# PiHAT_v0_2.net
KiCad netlist of a schematic drawn in EAGLE
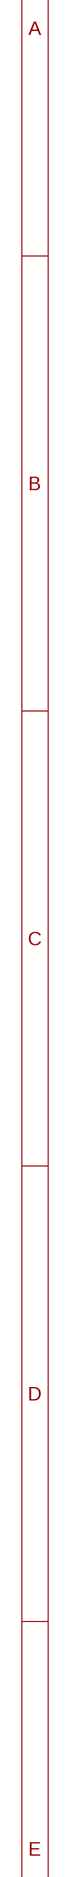
[diagram p0: schematic, sheet 1, part 1 of 2]
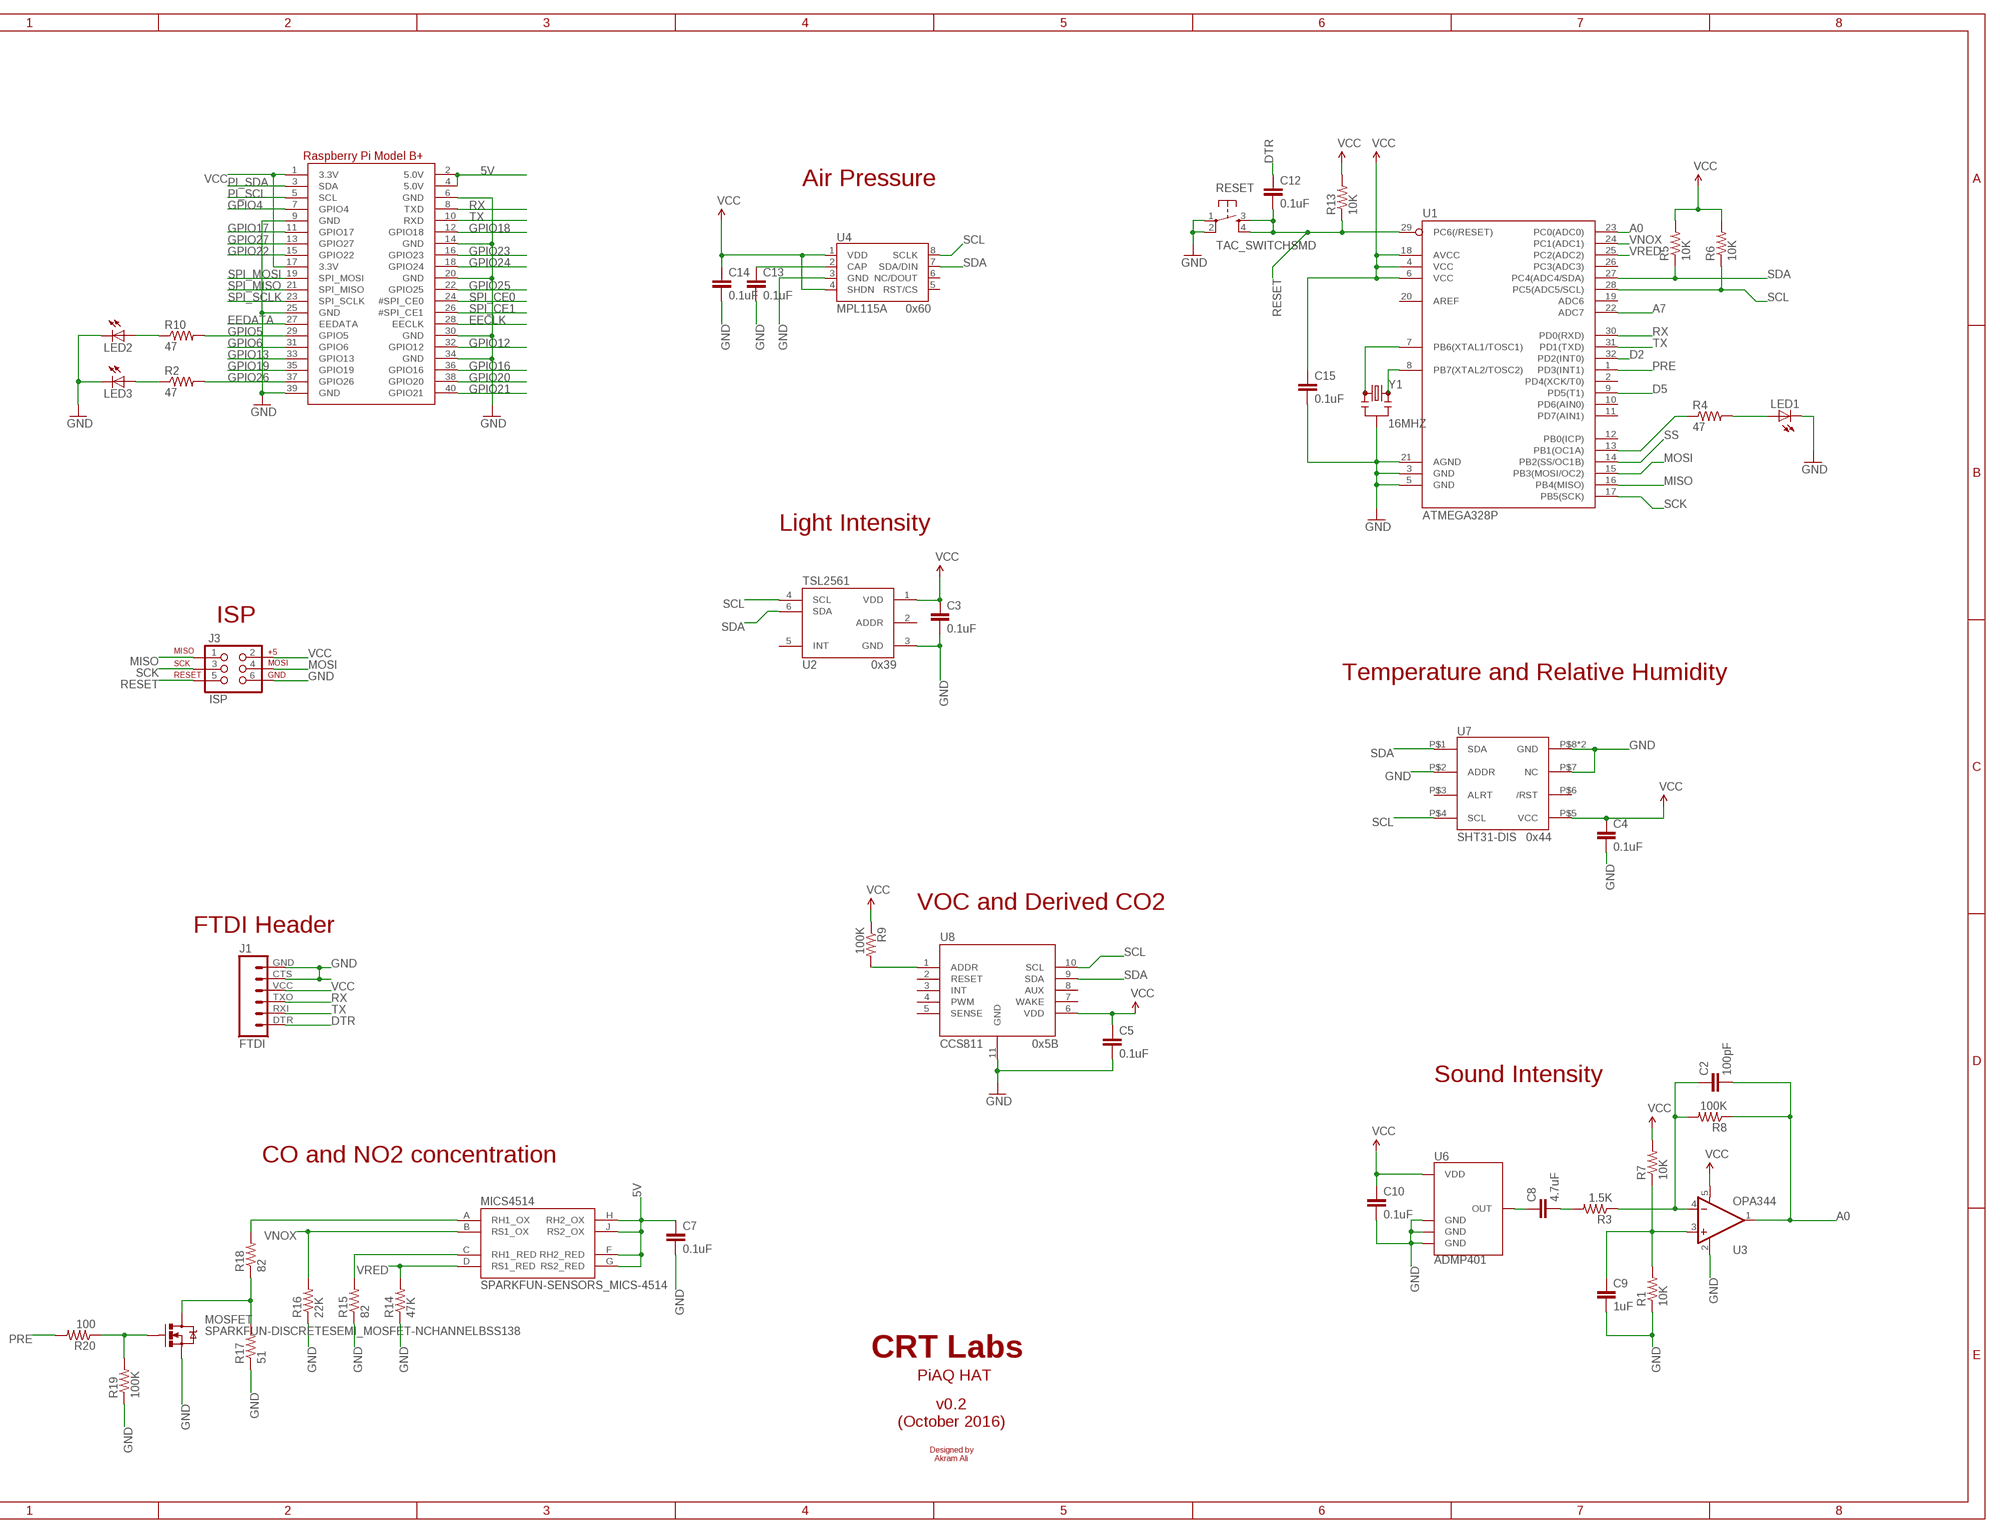
[diagram p1: schematic, sheet 1, part 2 of 2]

(export (version "E")
  (design (tool "Eeschema 10.0.6"))
  (components
    (comp (ref "C2")
      (value "100pF")
      (footprint "eagle-import:0805")
      (fields (field (name "MPN") "CC0805JRNPO9BN101"))
      (libsource (lib "eagle-import") (part "CAP0805"))
    )
    (comp (ref "C3")
      (value "0.1uF")
      (footprint "eagle-import:0805")
      (fields (field (name "MPN") "CC0603KRX7R7BB104"))
      (libsource (lib "eagle-import") (part "SparkFun-Passives_CAP0805"))
    )
    (comp (ref "C4")
      (value "0.1uF")
      (footprint "eagle-import:0805")
      (fields (field (name "MPN") "CC0603KRX7R7BB104"))
      (libsource (lib "eagle-import") (part "SparkFun-Passives_CAP0805"))
    )
    (comp (ref "C5")
      (value "0.1uF")
      (footprint "eagle-import:0805")
      (fields (field (name "MPN") "CC0603KRX7R7BB104"))
      (libsource (lib "eagle-import") (part "SparkFun-Passives_CAP0805"))
    )
    (comp (ref "C7")
      (value "0.1uF")
      (footprint "eagle-import:0805")
      (fields (field (name "MPN") "CC0603KRX7R7BB104"))
      (libsource (lib "eagle-import") (part "SparkFun-Passives_CAP0805"))
    )
    (comp (ref "C8")
      (value "4.7uF")
      (footprint "eagle-import:0805")
      (fields (field (name "MPN") "CC0805KKX5R8BB475"))
      (libsource (lib "eagle-import") (part "CAP0805"))
    )
    (comp (ref "C9")
      (value "1uF")
      (footprint "eagle-import:0805")
      (fields (field (name "MPN") "CC0805KKX7R7BB105"))
      (libsource (lib "eagle-import") (part "CAP0805"))
    )
    (comp (ref "C10")
      (value "0.1uF")
      (footprint "eagle-import:0805")
      (fields (field (name "MPN") "CC0603KRX7R7BB104"))
      (libsource (lib "eagle-import") (part "CAP0805"))
    )
    (comp (ref "C12")
      (value "0.1uF")
      (footprint "eagle-import:0805")
      (fields (field (name "MPN") "CC0603KRX7R7BB104"))
      (libsource (lib "eagle-import") (part "SparkFun-Passives_CAP0805"))
    )
    (comp (ref "C13")
      (value "0.1uF")
      (footprint "eagle-import:0805")
      (fields (field (name "MPN") "CC0603KRX7R7BB104"))
      (libsource (lib "eagle-import") (part "SparkFun-Passives_CAP0805"))
    )
    (comp (ref "C14")
      (value "0.1uF")
      (footprint "eagle-import:0805")
      (fields (field (name "MPN") "CC0603KRX7R7BB104"))
      (libsource (lib "eagle-import") (part "SparkFun-Passives_CAP0805"))
    )
    (comp (ref "C15")
      (value "0.1uF")
      (footprint "eagle-import:0805")
      (fields (field (name "MPN") "CC0603KRX7R7BB104"))
      (libsource (lib "eagle-import") (part "SparkFun-Passives_CAP0805"))
    )
    (comp (ref "J1")
      (value "FTDI")
      (footprint "eagle-import:FTDI_BASIC")
      (fields (field (name "MPN") "FT231XS-R"))
      (libsource (lib "eagle-import") (part "FTDI_BASICPTH"))
    )
    (comp (ref "J3")
      (value "ISP")
      (footprint "eagle-import:2X3")
      (libsource (lib "eagle-import") (part "AVR_SPI_PRG_6PTH"))
    )
    (comp (ref "LED1")
      (value "LEDCHIPLED_0805")
      (footprint "eagle-import:CHIPLED_0805")
      (fields (field (name "MPN") "LY L29K-H1K2-26-Z"))
      (libsource (lib "eagle-import") (part "LEDCHIPLED_0805"))
    )
    (comp (ref "LED2")
      (value "LEDCHIPLED_0805")
      (footprint "eagle-import:CHIPLED_0805")
      (description "LED")
      (fields (field (name "MPN") "LY L29K-H1K2-26-Z"))
      (libsource (lib "eagle-import") (part "LEDCHIPLED_0805"))
    )
    (comp (ref "LED3")
      (value "LEDCHIPLED_0805")
      (footprint "eagle-import:CHIPLED_0805")
      (description "LED")
      (fields (field (name "MPN") "LY L29K-H1K2-26-Z"))
      (libsource (lib "eagle-import") (part "LEDCHIPLED_0805"))
    )
    (comp (ref "MICS4514")
      (value "SPARKFUN-SENSORS_MICS-4514")
      (footprint "eagle-import:SPARKFUN-SENSORS_MICS_10-SMD")
      (fields (field (name "MANF") "SensorTech") (field (name "MPN") "MiCS-4514"))
      (libsource (lib "eagle-import") (part "SPARKFUN-SENSORS_MICS-4514"))
    )
    (comp (ref "MOSFET")
      (value "SPARKFUN-DISCRETESEMI_MOSFET-NCHANNELBSS138")
      (footprint "eagle-import:SPARKFUN-DISCRETESEMI_SOT23-3")
      (fields (field (name "MPN") "BSS138-7-F"))
      (libsource (lib "eagle-import") (part "SPARKFUN-DISCRETESEMI_MOSFET-NCHANNELBSS138"))
    )
    (comp (ref "R1")
      (value "10K")
      (footprint "eagle-import:0805")
      (fields (field (name "MPN") "RC0805JR-0710KL"))
      (libsource (lib "eagle-import") (part "RESISTOR0805-RES"))
    )
    (comp (ref "R2")
      (value "47")
      (footprint "eagle-import:0805")
      (fields (field (name "MPN") "RC0805JR-0747RL"))
      (libsource (lib "eagle-import") (part "SparkFun-Resistors_RESISTOR0805-RES"))
    )
    (comp (ref "R3")
      (value "1.5K")
      (footprint "eagle-import:0805")
      (fields (field (name "MPN") "RT0805BRD071K5L"))
      (libsource (lib "eagle-import") (part "RESISTOR0805-RES"))
    )
    (comp (ref "R4")
      (value "47")
      (footprint "eagle-import:0805")
      (fields (field (name "MPN") "RC0805JR-0747RL"))
      (libsource (lib "eagle-import") (part "SparkFun-Resistors_RESISTOR0805-RES"))
    )
    (comp (ref "R5")
      (value "10K")
      (footprint "eagle-import:0805")
      (fields (field (name "MPN") "RC0805JR-0710KL"))
      (libsource (lib "eagle-import") (part "SparkFun-Resistors_RESISTOR0805-RES"))
    )
    (comp (ref "R6")
      (value "10K")
      (footprint "eagle-import:0805")
      (fields (field (name "MPN") "RC0805JR-0710KL"))
      (libsource (lib "eagle-import") (part "SparkFun-Resistors_RESISTOR0805-RES"))
    )
    (comp (ref "R7")
      (value "10K")
      (footprint "eagle-import:0805")
      (fields (field (name "MPN") "RC0805JR-0710KL"))
      (libsource (lib "eagle-import") (part "RESISTOR0805-RES"))
    )
    (comp (ref "R8")
      (value "100K")
      (footprint "eagle-import:0805")
      (fields (field (name "MPN") "RC0805FR-07100KL"))
      (libsource (lib "eagle-import") (part "RESISTOR0805-RES"))
    )
    (comp (ref "R9")
      (value "100K")
      (footprint "eagle-import:0805")
      (fields (field (name "MPN") "RC0805FR-07100KL"))
      (libsource (lib "eagle-import") (part "RESISTOR0805-RES"))
    )
    (comp (ref "R10")
      (value "47")
      (footprint "eagle-import:0805")
      (fields (field (name "MPN") "RC0805JR-0747RL"))
      (libsource (lib "eagle-import") (part "SparkFun-Resistors_RESISTOR0805-RES"))
    )
    (comp (ref "R13")
      (value "10K")
      (footprint "eagle-import:0805")
      (fields (field (name "MPN") "RC0805JR-0710KL"))
      (libsource (lib "eagle-import") (part "RESISTOR0805-RES"))
    )
    (comp (ref "R14")
      (value "47K")
      (footprint "eagle-import:0805")
      (fields (field (name "MPN") "ESR10EZPJ473"))
      (libsource (lib "eagle-import") (part "RESISTOR0805-RES"))
    )
    (comp (ref "R15")
      (value "82")
      (footprint "eagle-import:0805")
      (fields (field (name "MPN") "CRCW080582R0FKEA"))
      (libsource (lib "eagle-import") (part "RESISTOR0805-RES"))
    )
    (comp (ref "R16")
      (value "22K")
      (footprint "eagle-import:0805")
      (fields (field (name "MPN") "RC0805JR-0722KL"))
      (libsource (lib "eagle-import") (part "RESISTOR0805-RES"))
    )
    (comp (ref "R17")
      (value "51")
      (footprint "eagle-import:0805")
      (fields (field (name "MPN") "ESR10EZPJ510"))
      (libsource (lib "eagle-import") (part "RESISTOR0805-RES"))
    )
    (comp (ref "R18")
      (value "82")
      (footprint "eagle-import:0805")
      (fields (field (name "MPN") "CRCW080582R0FKEA"))
      (libsource (lib "eagle-import") (part "RESISTOR0805-RES"))
    )
    (comp (ref "R19")
      (value "100K")
      (footprint "eagle-import:0805")
      (fields (field (name "MPN") "RC0805FR-07100KL"))
      (libsource (lib "eagle-import") (part "RESISTOR0805-RES"))
    )
    (comp (ref "R20")
      (value "100")
      (footprint "eagle-import:0805")
      (fields (field (name "MPN") "RC0805FR-07100RL"))
      (libsource (lib "eagle-import") (part "RESISTOR0805-RES"))
    )
    (comp (ref "RESET")
      (value "TAC_SWITCHSMD")
      (footprint "eagle-import:TACTILE-SWITCH-SMD")
      (fields (field (name "MPN") "PTS525SM15SMTR2 LFS"))
      (libsource (lib "eagle-import") (part "TAC_SWITCHSMD"))
    )
    (comp (ref "RPI1")
      (value "RASPBERRYPI_BPLUS_HATSLOTS")
      (footprint "eagle-import:PI_HAT_SLOTS")
      (libsource (lib "eagle-import") (part "RASPBERRYPI_BPLUS_HATSLOTS"))
    )
    (comp (ref "U1")
      (value "ATMEGA328P")
      (footprint "eagle-import:TQFP32-08")
      (fields (field (name "MPN") "ATMEGA328PB-AU"))
      (libsource (lib "eagle-import") (part "ATMEGA328P_TQFP"))
    )
    (comp (ref "U2")
      (value "TSL2561")
      (footprint "eagle-import:FN-6")
      (fields (field (name "MANF") "AMS-TAOS-USA-Inc.") (field (name "MPN") "TSL2561FN"))
      (libsource (lib "eagle-import") (part "TSL2561FN"))
    )
    (comp (ref "U3")
      (value "OPA344")
      (footprint "eagle-import:SOT23-5")
      (fields (field (name "MPN") "OPA344NA/3K"))
      (libsource (lib "eagle-import") (part "OPA344"))
    )
    (comp (ref "U4")
      (value "MPL115A")
      (footprint "eagle-import:LGA8")
      (fields (field (name "MPN") "MPL115A2"))
      (libsource (lib "eagle-import") (part "MPL115A"))
    )
    (comp (ref "U6")
      (value "ADMP401")
      (footprint "eagle-import:ADMP401")
      (fields (field (name "MPN") "INMP401ACEZ-R7"))
      (libsource (lib "eagle-import") (part "ADMP401"))
    )
    (comp (ref "U7")
      (value "SHT31-DIS")
      (footprint "eagle-import:SHT3X")
      (fields (field (name "MPN") "SHT31-DIS-B"))
      (libsource (lib "eagle-import") (part "SHT31-DIS"))
    )
    (comp (ref "U8")
      (value "CCS811")
      (footprint "eagle-import:LGA")
      (fields (field (name "MANF") "AMS"))
      (libsource (lib "eagle-import") (part "CCS811-I2C"))
    )
    (comp (ref "Y1")
      (value "16MHZ")
      (footprint "eagle-import:RESONATOR-SMD")
      (fields (field (name "MPN") "CSTCE16M0V53-R0"))
      (libsource (lib "eagle-import") (part "RESONATOR16MHZ"))
    )
  )
  (nets
    (net (code "1") (name "/EECLK") (class "Default")
      (node (ref "RPI1") (pin "28") (pinfunction "EECLK_28") (pintype "power_in"))
    )
    (net (code "2") (name "/EEDATA") (class "Default")
      (node (ref "RPI1") (pin "27") (pinfunction "EEDATA_27") (pintype "bidirectional"))
    )
    (net (code "3") (name "/GPIO4") (class "Default")
      (node (ref "RPI1") (pin "7") (pinfunction "GPIO4_7") (pintype "bidirectional"))
    )
    (net (code "4") (name "/GPIO5") (class "Default")
      (node (ref "R10") (pin "2") (pinfunction "2_2") (pintype "passive"))
      (node (ref "RPI1") (pin "29") (pinfunction "GPIO5_29") (pintype "bidirectional"))
    )
    (net (code "5") (name "/GPIO6") (class "Default")
      (node (ref "RPI1") (pin "31") (pinfunction "GPIO6_31") (pintype "power_in"))
    )
    (net (code "6") (name "/GPIO12") (class "Default")
      (node (ref "RPI1") (pin "32") (pinfunction "GPIO12_32") (pintype "bidirectional"))
    )
    (net (code "7") (name "/GPIO13") (class "Default")
      (node (ref "RPI1") (pin "33") (pinfunction "GPIO13_33") (pintype "bidirectional"))
    )
    (net (code "8") (name "/GPIO16") (class "Default")
      (node (ref "RPI1") (pin "36") (pinfunction "GPIO16_36") (pintype "power_in"))
    )
    (net (code "9") (name "/GPIO17") (class "Default")
      (node (ref "RPI1") (pin "11") (pinfunction "GPIO17_11") (pintype "bidirectional"))
    )
    (net (code "10") (name "/GPIO18") (class "Default")
      (node (ref "RPI1") (pin "12") (pinfunction "GPIO18_12") (pintype "bidirectional"))
    )
    (net (code "11") (name "/GPIO19") (class "Default")
      (node (ref "RPI1") (pin "35") (pinfunction "GPIO19_35") (pintype "bidirectional"))
    )
    (net (code "12") (name "/GPIO20") (class "Default")
      (node (ref "RPI1") (pin "38") (pinfunction "GPIO20_38") (pintype "bidirectional"))
    )
    (net (code "13") (name "/GPIO21") (class "Default")
      (node (ref "RPI1") (pin "40") (pinfunction "GPIO21_40") (pintype "bidirectional"))
    )
    (net (code "14") (name "/GPIO22") (class "Default")
      (node (ref "RPI1") (pin "15") (pinfunction "GPIO22_15") (pintype "bidirectional"))
    )
    (net (code "15") (name "/GPIO23") (class "Default")
      (node (ref "RPI1") (pin "16") (pinfunction "GPIO23_16") (pintype "bidirectional"))
    )
    (net (code "16") (name "/GPIO24") (class "Default")
      (node (ref "RPI1") (pin "18") (pinfunction "GPIO24_18") (pintype "bidirectional"))
    )
    (net (code "17") (name "/GPIO25") (class "Default")
      (node (ref "RPI1") (pin "22") (pinfunction "GPIO25_22") (pintype "bidirectional"))
    )
    (net (code "18") (name "/GPIO26") (class "Default")
      (node (ref "R2") (pin "2") (pinfunction "2_2") (pintype "passive"))
      (node (ref "RPI1") (pin "37") (pinfunction "GPIO26_37") (pintype "bidirectional"))
    )
    (net (code "19") (name "/GPIO27") (class "Default")
      (node (ref "RPI1") (pin "13") (pinfunction "GPIO27_13") (pintype "bidirectional"))
    )
    (net (code "20") (name "/PI_SCL") (class "Default")
      (node (ref "RPI1") (pin "5") (pinfunction "SCL_5") (pintype "bidirectional"))
    )
    (net (code "21") (name "/PI_SDA") (class "Default")
      (node (ref "RPI1") (pin "3") (pinfunction "SDA_3") (pintype "bidirectional"))
    )
    (net (code "22") (name "/SPI_CE0") (class "Default")
      (node (ref "RPI1") (pin "24") (pinfunction "#SPI_CE0_24") (pintype "bidirectional"))
    )
    (net (code "23") (name "/SPI_CE1") (class "Default")
      (node (ref "RPI1") (pin "26") (pinfunction "#SPI_CE1_26") (pintype "bidirectional"))
    )
    (net (code "24") (name "/SPI_MISO") (class "Default")
      (node (ref "RPI1") (pin "21") (pinfunction "SPI_MISO_21") (pintype "bidirectional"))
    )
    (net (code "25") (name "/SPI_MOSI") (class "Default")
      (node (ref "RPI1") (pin "19") (pinfunction "SPI_MOSI_19") (pintype "bidirectional"))
    )
    (net (code "26") (name "/SPI_SCLK") (class "Default")
      (node (ref "RPI1") (pin "23") (pinfunction "SPI_SCLK_23") (pintype "bidirectional"))
    )
    (net (code "27") (name "5V") (class "Default")
      (node (ref "C7") (pin "1") (pinfunction "1_1") (pintype "passive"))
      (node (ref "MICS4514") (pin "F") (pinfunction "RH2_RED_F") (pintype "bidirectional"))
      (node (ref "MICS4514") (pin "G") (pinfunction "RS2_RED_G") (pintype "bidirectional"))
      (node (ref "MICS4514") (pin "H") (pinfunction "RH2_OX_H") (pintype "bidirectional"))
      (node (ref "MICS4514") (pin "J") (pinfunction "RS2_OX_J") (pintype "bidirectional"))
      (node (ref "RPI1") (pin "2") (pinfunction "5.0V_2") (pintype "power_in"))
      (node (ref "RPI1") (pin "4") (pinfunction "5.0V_4") (pintype "power_in"))
    )
    (net (code "28") (name "A0") (class "Default")
      (node (ref "C2") (pin "2") (pinfunction "2_2") (pintype "passive"))
      (node (ref "R8") (pin "1") (pinfunction "1_1") (pintype "passive"))
      (node (ref "U1") (pin "23") (pinfunction "PC0(ADC0)_23") (pintype "bidirectional"))
      (node (ref "U3") (pin "1") (pinfunction "OUT_1") (pintype "output"))
    )
    (net (code "29") (name "A7") (class "Default")
      (node (ref "U1") (pin "22") (pinfunction "ADC7_22") (pintype "bidirectional"))
    )
    (net (code "30") (name "D2") (class "Default")
      (node (ref "U1") (pin "32") (pinfunction "PD2(INT0)_32") (pintype "bidirectional"))
    )
    (net (code "31") (name "D5") (class "Default")
      (node (ref "U1") (pin "9") (pinfunction "PD5(T1)_9") (pintype "bidirectional"))
    )
    (net (code "32") (name "DTR") (class "Default")
      (node (ref "C12") (pin "1") (pinfunction "1_1") (pintype "passive"))
      (node (ref "J1") (pin "DTR") (pinfunction "1_DTR") (pintype "passive"))
    )
    (net (code "33") (name "GND") (class "Default")
      (node (ref "C10") (pin "2") (pinfunction "2_2") (pintype "passive"))
      (node (ref "C13") (pin "2") (pinfunction "2_2") (pintype "passive"))
      (node (ref "C14") (pin "2") (pinfunction "2_2") (pintype "passive"))
      (node (ref "C15") (pin "2") (pinfunction "2_2") (pintype "passive"))
      (node (ref "C3") (pin "2") (pinfunction "2_2") (pintype "passive"))
      (node (ref "C4") (pin "2") (pinfunction "2_2") (pintype "passive"))
      (node (ref "C5") (pin "2") (pinfunction "2_2") (pintype "passive"))
      (node (ref "C7") (pin "2") (pinfunction "2_2") (pintype "passive"))
      (node (ref "C9") (pin "2") (pinfunction "2_2") (pintype "passive"))
      (node (ref "J1") (pin "CTS") (pinfunction "5_CTS") (pintype "passive"))
      (node (ref "J1") (pin "GND") (pinfunction "6_GND") (pintype "passive"))
      (node (ref "J3") (pin "6") (pinfunction "6_6") (pintype "passive"))
      (node (ref "LED1") (pin "C") (pinfunction "C_C") (pintype "passive"))
      (node (ref "LED2") (pin "C") (pinfunction "C_C") (pintype "passive"))
      (node (ref "LED3") (pin "C") (pinfunction "C_C") (pintype "passive"))
      (node (ref "MOSFET") (pin "2") (pinfunction "S_2") (pintype "passive"))
      (node (ref "R1") (pin "1") (pinfunction "1_1") (pintype "passive"))
      (node (ref "R14") (pin "1") (pinfunction "1_1") (pintype "passive"))
      (node (ref "R15") (pin "1") (pinfunction "1_1") (pintype "passive"))
      (node (ref "R16") (pin "1") (pinfunction "1_1") (pintype "passive"))
      (node (ref "R17") (pin "1") (pinfunction "1_1") (pintype "passive"))
      (node (ref "R19") (pin "1") (pinfunction "1_1") (pintype "passive"))
      (node (ref "RESET") (pin "1") (pinfunction "1_1") (pintype "passive"))
      (node (ref "RESET") (pin "2") (pinfunction "2_2") (pintype "passive"))
      (node (ref "RPI1") (pin "14") (pinfunction "GND_14") (pintype "power_in"))
      (node (ref "RPI1") (pin "20") (pinfunction "GND_20") (pintype "power_in"))
      (node (ref "RPI1") (pin "25") (pinfunction "GND_25") (pintype "power_in"))
      (node (ref "RPI1") (pin "30") (pinfunction "GND_30") (pintype "bidirectional"))
      (node (ref "RPI1") (pin "34") (pinfunction "GND_34") (pintype "bidirectional"))
      (node (ref "RPI1") (pin "39") (pinfunction "GND_39") (pintype "power_in"))
      (node (ref "RPI1") (pin "6") (pinfunction "GND_6") (pintype "power_in"))
      (node (ref "RPI1") (pin "9") (pinfunction "GND_9") (pintype "power_in"))
      (node (ref "U1") (pin "21") (pinfunction "AGND_21") (pintype "bidirectional"))
      (node (ref "U1") (pin "3") (pinfunction "GND_3") (pintype "bidirectional"))
      (node (ref "U1") (pin "5") (pinfunction "GND_5") (pintype "bidirectional"))
      (node (ref "U2") (pin "3") (pinfunction "GND_3") (pintype "power_in"))
      (node (ref "U3") (pin "2") (pinfunction "V-_2") (pintype "power_in"))
      (node (ref "U4") (pin "3") (pinfunction "GND_3") (pintype "bidirectional"))
      (node (ref "U6") (pin "2") (pinfunction "GND_2") (pintype "bidirectional"))
      (node (ref "U6") (pin "4") (pinfunction "GND_4") (pintype "bidirectional"))
      (node (ref "U6") (pin "6") (pinfunction "GND_6") (pintype "bidirectional"))
      (node (ref "U7") (pin "P$2") (pinfunction "ADDR_P$2") (pintype "bidirectional"))
      (node (ref "U7") (pin "P$7") (pinfunction "NC_P$7") (pintype "bidirectional"))
      (node (ref "U7") (pin "P$8") (pinfunction "GND_P$8") (pintype "bidirectional"))
      (node (ref "U7") (pin "PAD") (pinfunction "GND_PAD") (pintype "bidirectional"))
      (node (ref "U8") (pin "11") (pinfunction "GND_11") (pintype "bidirectional"))
      (node (ref "Y1") (pin "2") (pinfunction "2_2") (pintype "passive"))
    )
    (net (code "34") (name "MISO") (class "Default")
      (node (ref "J3") (pin "1") (pinfunction "1_1") (pintype "passive"))
      (node (ref "U1") (pin "16") (pinfunction "PB4(MISO)_16") (pintype "bidirectional"))
    )
    (net (code "35") (name "MOSI") (class "Default")
      (node (ref "J3") (pin "4") (pinfunction "4_4") (pintype "passive"))
      (node (ref "U1") (pin "15") (pinfunction "PB3(MOSI/OC2)_15") (pintype "bidirectional"))
    )
    (net (code "36") (name "Net-(C8-Pad2)") (class "Default")
      (node (ref "C8") (pin "2") (pinfunction "2_2") (pintype "passive"))
      (node (ref "R3") (pin "2") (pinfunction "2_2") (pintype "passive"))
    )
    (net (code "37") (name "Net-(LED1-PadA)") (class "Default")
      (node (ref "LED1") (pin "A") (pinfunction "A_A") (pintype "passive"))
      (node (ref "R4") (pin "2") (pinfunction "2_2") (pintype "passive"))
    )
    (net (code "38") (name "Net-(LED2-PadA)") (class "Default")
      (node (ref "LED2") (pin "A") (pinfunction "A_A") (pintype "passive"))
      (node (ref "R10") (pin "1") (pinfunction "1_1") (pintype "passive"))
    )
    (net (code "39") (name "Net-(LED3-PadA)") (class "Default")
      (node (ref "LED3") (pin "A") (pinfunction "A_A") (pintype "passive"))
      (node (ref "R2") (pin "1") (pinfunction "1_1") (pintype "passive"))
    )
    (net (code "40") (name "Net-(MICS4514-RH1_OX)") (class "Default")
      (node (ref "MICS4514") (pin "A") (pinfunction "RH1_OX_A") (pintype "bidirectional"))
      (node (ref "R18") (pin "2") (pinfunction "2_2") (pintype "passive"))
    )
    (net (code "41") (name "Net-(MICS4514-RH1_RED)") (class "Default")
      (node (ref "MICS4514") (pin "C") (pinfunction "RH1_RED_C") (pintype "bidirectional"))
      (node (ref "R15") (pin "2") (pinfunction "2_2") (pintype "passive"))
    )
    (net (code "42") (name "Net-(MOSFET-D)") (class "Default")
      (node (ref "MOSFET") (pin "3") (pinfunction "D_3") (pintype "passive"))
      (node (ref "R17") (pin "2") (pinfunction "2_2") (pintype "passive"))
      (node (ref "R18") (pin "1") (pinfunction "1_1") (pintype "passive"))
    )
    (net (code "43") (name "Net-(MOSFET-G)") (class "Default")
      (node (ref "MOSFET") (pin "1") (pinfunction "G_1") (pintype "passive"))
      (node (ref "R19") (pin "2") (pinfunction "2_2") (pintype "passive"))
      (node (ref "R20") (pin "1") (pinfunction "1_1") (pintype "passive"))
    )
    (net (code "44") (name "Net-(U1-PB1(OC1A))") (class "Default")
      (node (ref "R4") (pin "1") (pinfunction "1_1") (pintype "passive"))
      (node (ref "U1") (pin "13") (pinfunction "PB1(OC1A)_13") (pintype "bidirectional"))
    )
    (net (code "45") (name "Net-(U1-PB6(XTAL1{slash}TOSC1))") (class "Default")
      (node (ref "U1") (pin "7") (pinfunction "PB6(XTAL1/TOSC1)_7") (pintype "bidirectional"))
      (node (ref "Y1") (pin "1") (pinfunction "1_1") (pintype "passive"))
    )
    (net (code "46") (name "Net-(U1-PB7(XTAL2{slash}TOSC2))") (class "Default")
      (node (ref "U1") (pin "8") (pinfunction "PB7(XTAL2/TOSC2)_8") (pintype "bidirectional"))
      (node (ref "Y1") (pin "3") (pinfunction "3_3") (pintype "passive"))
    )
    (net (code "47") (name "Net-(U3-+IN)") (class "Default")
      (node (ref "C9") (pin "1") (pinfunction "1_1") (pintype "passive"))
      (node (ref "R1") (pin "2") (pinfunction "2_2") (pintype "passive"))
      (node (ref "R7") (pin "1") (pinfunction "1_1") (pintype "passive"))
      (node (ref "U3") (pin "3") (pinfunction "+IN_3") (pintype "input"))
    )
    (net (code "48") (name "Net-(U3--IN)") (class "Default")
      (node (ref "C2") (pin "1") (pinfunction "1_1") (pintype "passive"))
      (node (ref "R3") (pin "1") (pinfunction "1_1") (pintype "passive"))
      (node (ref "R8") (pin "2") (pinfunction "2_2") (pintype "passive"))
      (node (ref "U3") (pin "4") (pinfunction "-IN_4") (pintype "input"))
    )
    (net (code "49") (name "Net-(U4-CAP)") (class "Default")
      (node (ref "C13") (pin "1") (pinfunction "1_1") (pintype "passive"))
      (node (ref "U4") (pin "2") (pinfunction "CAP_2") (pintype "bidirectional"))
    )
    (net (code "50") (name "Net-(U6-OUT)") (class "Default")
      (node (ref "C8") (pin "1") (pinfunction "1_1") (pintype "passive"))
      (node (ref "U6") (pin "1") (pinfunction "OUT_1") (pintype "bidirectional"))
    )
    (net (code "51") (name "Net-(U8-ADDR)") (class "Default")
      (node (ref "R9") (pin "2") (pinfunction "2_2") (pintype "passive"))
      (node (ref "U8") (pin "1") (pinfunction "ADDR_1") (pintype "bidirectional"))
    )
    (net (code "52") (name "PRE") (class "Default")
      (node (ref "R20") (pin "2") (pinfunction "2_2") (pintype "passive"))
      (node (ref "U1") (pin "1") (pinfunction "PD3(INT1)_1") (pintype "bidirectional"))
    )
    (net (code "53") (name "RESET") (class "Default")
      (node (ref "C12") (pin "2") (pinfunction "2_2") (pintype "passive"))
      (node (ref "J3") (pin "5") (pinfunction "5_5") (pintype "passive"))
      (node (ref "R13") (pin "1") (pinfunction "1_1") (pintype "passive"))
      (node (ref "RESET") (pin "3") (pinfunction "3_3") (pintype "passive"))
      (node (ref "RESET") (pin "4") (pinfunction "4_4") (pintype "passive"))
      (node (ref "U1") (pin "29") (pinfunction "PC6(/RESET)_29") (pintype "bidirectional"))
    )
    (net (code "54") (name "RX") (class "Default")
      (node (ref "J1") (pin "TXO") (pinfunction "3_TXO") (pintype "passive"))
      (node (ref "RPI1") (pin "8") (pinfunction "TXD_8") (pintype "output"))
      (node (ref "U1") (pin "30") (pinfunction "PD0(RXD)_30") (pintype "bidirectional"))
    )
    (net (code "55") (name "SCK") (class "Default")
      (node (ref "J3") (pin "3") (pinfunction "3_3") (pintype "passive"))
      (node (ref "U1") (pin "17") (pinfunction "PB5(SCK)_17") (pintype "bidirectional"))
    )
    (net (code "56") (name "SCL") (class "Default")
      (node (ref "R6") (pin "1") (pinfunction "1_1") (pintype "passive"))
      (node (ref "U1") (pin "28") (pinfunction "PC5(ADC5/SCL)_28") (pintype "bidirectional"))
      (node (ref "U2") (pin "4") (pinfunction "SCL_4") (pintype "input"))
      (node (ref "U4") (pin "8") (pinfunction "SCLK_8") (pintype "bidirectional"))
      (node (ref "U7") (pin "P$4") (pinfunction "SCL_P$4") (pintype "bidirectional"))
      (node (ref "U8") (pin "10") (pinfunction "SCL_10") (pintype "bidirectional"))
    )
    (net (code "57") (name "SDA") (class "Default")
      (node (ref "R5") (pin "1") (pinfunction "1_1") (pintype "passive"))
      (node (ref "U1") (pin "27") (pinfunction "PC4(ADC4/SDA)_27") (pintype "bidirectional"))
      (node (ref "U2") (pin "6") (pinfunction "SDA_6") (pintype "bidirectional"))
      (node (ref "U4") (pin "7") (pinfunction "SDA/DIN_7") (pintype "bidirectional"))
      (node (ref "U7") (pin "P$1") (pinfunction "SDA_P$1") (pintype "bidirectional"))
      (node (ref "U8") (pin "9") (pinfunction "SDA_9") (pintype "bidirectional"))
    )
    (net (code "58") (name "SS") (class "Default")
      (node (ref "U1") (pin "14") (pinfunction "PB2(SS/OC1B)_14") (pintype "bidirectional"))
    )
    (net (code "59") (name "TX") (class "Default")
      (node (ref "J1") (pin "RXI") (pinfunction "2_RXI") (pintype "passive"))
      (node (ref "RPI1") (pin "10") (pinfunction "RXD_10") (pintype "bidirectional"))
      (node (ref "U1") (pin "31") (pinfunction "PD1(TXD)_31") (pintype "bidirectional"))
    )
    (net (code "60") (name "VCC") (class "Default")
      (node (ref "C10") (pin "1") (pinfunction "1_1") (pintype "passive"))
      (node (ref "C14") (pin "1") (pinfunction "1_1") (pintype "passive"))
      (node (ref "C15") (pin "1") (pinfunction "1_1") (pintype "passive"))
      (node (ref "C3") (pin "1") (pinfunction "1_1") (pintype "passive"))
      (node (ref "C4") (pin "1") (pinfunction "1_1") (pintype "passive"))
      (node (ref "C5") (pin "1") (pinfunction "1_1") (pintype "passive"))
      (node (ref "J1") (pin "VCC") (pinfunction "4_VCC") (pintype "passive"))
      (node (ref "J3") (pin "2") (pinfunction "2_2") (pintype "passive"))
      (node (ref "R13") (pin "2") (pinfunction "2_2") (pintype "passive"))
      (node (ref "R5") (pin "2") (pinfunction "2_2") (pintype "passive"))
      (node (ref "R6") (pin "2") (pinfunction "2_2") (pintype "passive"))
      (node (ref "R7") (pin "2") (pinfunction "2_2") (pintype "passive"))
      (node (ref "R9") (pin "1") (pinfunction "1_1") (pintype "passive"))
      (node (ref "RPI1") (pin "1") (pinfunction "3.3V_1") (pintype "power_in"))
      (node (ref "RPI1") (pin "17") (pinfunction "3.3V_17") (pintype "power_in"))
      (node (ref "U1") (pin "18") (pinfunction "AVCC_18") (pintype "bidirectional"))
      (node (ref "U1") (pin "4") (pinfunction "VCC_4") (pintype "bidirectional"))
      (node (ref "U1") (pin "6") (pinfunction "VCC_6") (pintype "bidirectional"))
      (node (ref "U2") (pin "1") (pinfunction "VDD_1") (pintype "power_in"))
      (node (ref "U3") (pin "5") (pinfunction "V+_5") (pintype "power_in"))
      (node (ref "U4") (pin "1") (pinfunction "VDD_1") (pintype "bidirectional"))
      (node (ref "U4") (pin "4") (pinfunction "SHDN_4") (pintype "bidirectional"))
      (node (ref "U6") (pin "5") (pinfunction "VDD_5") (pintype "bidirectional"))
      (node (ref "U7") (pin "P$5") (pinfunction "VCC_P$5") (pintype "bidirectional"))
      (node (ref "U8") (pin "6") (pinfunction "VDD_6") (pintype "bidirectional"))
    )
    (net (code "61") (name "VNOX") (class "Default")
      (node (ref "MICS4514") (pin "B") (pinfunction "RS1_OX_B") (pintype "bidirectional"))
      (node (ref "R16") (pin "2") (pinfunction "2_2") (pintype "passive"))
      (node (ref "U1") (pin "24") (pinfunction "PC1(ADC1)_24") (pintype "bidirectional"))
    )
    (net (code "62") (name "VRED") (class "Default")
      (node (ref "MICS4514") (pin "D") (pinfunction "RS1_RED_D") (pintype "bidirectional"))
      (node (ref "R14") (pin "2") (pinfunction "2_2") (pintype "passive"))
      (node (ref "U1") (pin "25") (pinfunction "PC2(ADC2)_25") (pintype "bidirectional"))
    )
    (net (code "63") (name "unconnected-(U1-ADC6-Pad19)") (class "Default")
      (node (ref "U1") (pin "19") (pinfunction "ADC6_19") (pintype "bidirectional"))
    )
    (net (code "64") (name "unconnected-(U1-AREF-Pad20)") (class "Default")
      (node (ref "U1") (pin "20") (pinfunction "AREF_20") (pintype "bidirectional"))
    )
    (net (code "65") (name "unconnected-(U1-PB0(ICP)-Pad12)") (class "Default")
      (node (ref "U1") (pin "12") (pinfunction "PB0(ICP)_12") (pintype "bidirectional"))
    )
    (net (code "66") (name "unconnected-(U1-PC3(ADC3)-Pad26)") (class "Default")
      (node (ref "U1") (pin "26") (pinfunction "PC3(ADC3)_26") (pintype "bidirectional"))
    )
    (net (code "67") (name "unconnected-(U1-PD4(XCK{slash}T0)-Pad2)") (class "Default")
      (node (ref "U1") (pin "2") (pinfunction "PD4(XCK/T0)_2") (pintype "bidirectional"))
    )
    (net (code "68") (name "unconnected-(U1-PD6(AIN0)-Pad10)") (class "Default")
      (node (ref "U1") (pin "10") (pinfunction "PD6(AIN0)_10") (pintype "bidirectional"))
    )
    (net (code "69") (name "unconnected-(U1-PD7(AIN1)-Pad11)") (class "Default")
      (node (ref "U1") (pin "11") (pinfunction "PD7(AIN1)_11") (pintype "bidirectional"))
    )
    (net (code "70") (name "unconnected-(U2-ADDR-Pad2)") (class "Default")
      (node (ref "U2") (pin "2") (pinfunction "ADDR_2") (pintype "input"))
    )
    (net (code "71") (name "unconnected-(U2-INT-Pad5)") (class "Default")
      (node (ref "U2") (pin "5") (pinfunction "INT_5") (pintype "output"))
    )
    (net (code "72") (name "unconnected-(U4-NC{slash}DOUT-Pad6)") (class "Default")
      (node (ref "U4") (pin "6") (pinfunction "NC/DOUT_6") (pintype "bidirectional"))
    )
    (net (code "73") (name "unconnected-(U4-RST{slash}CS-Pad5)") (class "Default")
      (node (ref "U4") (pin "5") (pinfunction "RST/CS_5") (pintype "bidirectional"))
    )
    (net (code "74") (name "unconnected-(U7-ALRT-PadP$3)") (class "Default")
      (node (ref "U7") (pin "P$3") (pinfunction "ALRT_P$3") (pintype "bidirectional"))
    )
    (net (code "75") (name "unconnected-(U7-{slash}RST-PadP$6)") (class "Default")
      (node (ref "U7") (pin "P$6") (pinfunction "/RST_P$6") (pintype "bidirectional"))
    )
    (net (code "76") (name "unconnected-(U8-AUX-Pad8)") (class "Default")
      (node (ref "U8") (pin "8") (pinfunction "AUX_8") (pintype "bidirectional"))
    )
    (net (code "77") (name "unconnected-(U8-INT-Pad3)") (class "Default")
      (node (ref "U8") (pin "3") (pinfunction "INT_3") (pintype "bidirectional"))
    )
    (net (code "78") (name "unconnected-(U8-PWM-Pad4)") (class "Default")
      (node (ref "U8") (pin "4") (pinfunction "PWM_4") (pintype "bidirectional"))
    )
    (net (code "79") (name "unconnected-(U8-RESET-Pad2)") (class "Default")
      (node (ref "U8") (pin "2") (pinfunction "RESET_2") (pintype "bidirectional"))
    )
    (net (code "80") (name "unconnected-(U8-SENSE-Pad5)") (class "Default")
      (node (ref "U8") (pin "5") (pinfunction "SENSE_5") (pintype "bidirectional"))
    )
    (net (code "81") (name "unconnected-(U8-WAKE-Pad7)") (class "Default")
      (node (ref "U8") (pin "7") (pinfunction "WAKE_7") (pintype "bidirectional"))
    )
  )
)
